# SW_Regulator.net
KiCad netlist of a schematic drawn in Altium Designer
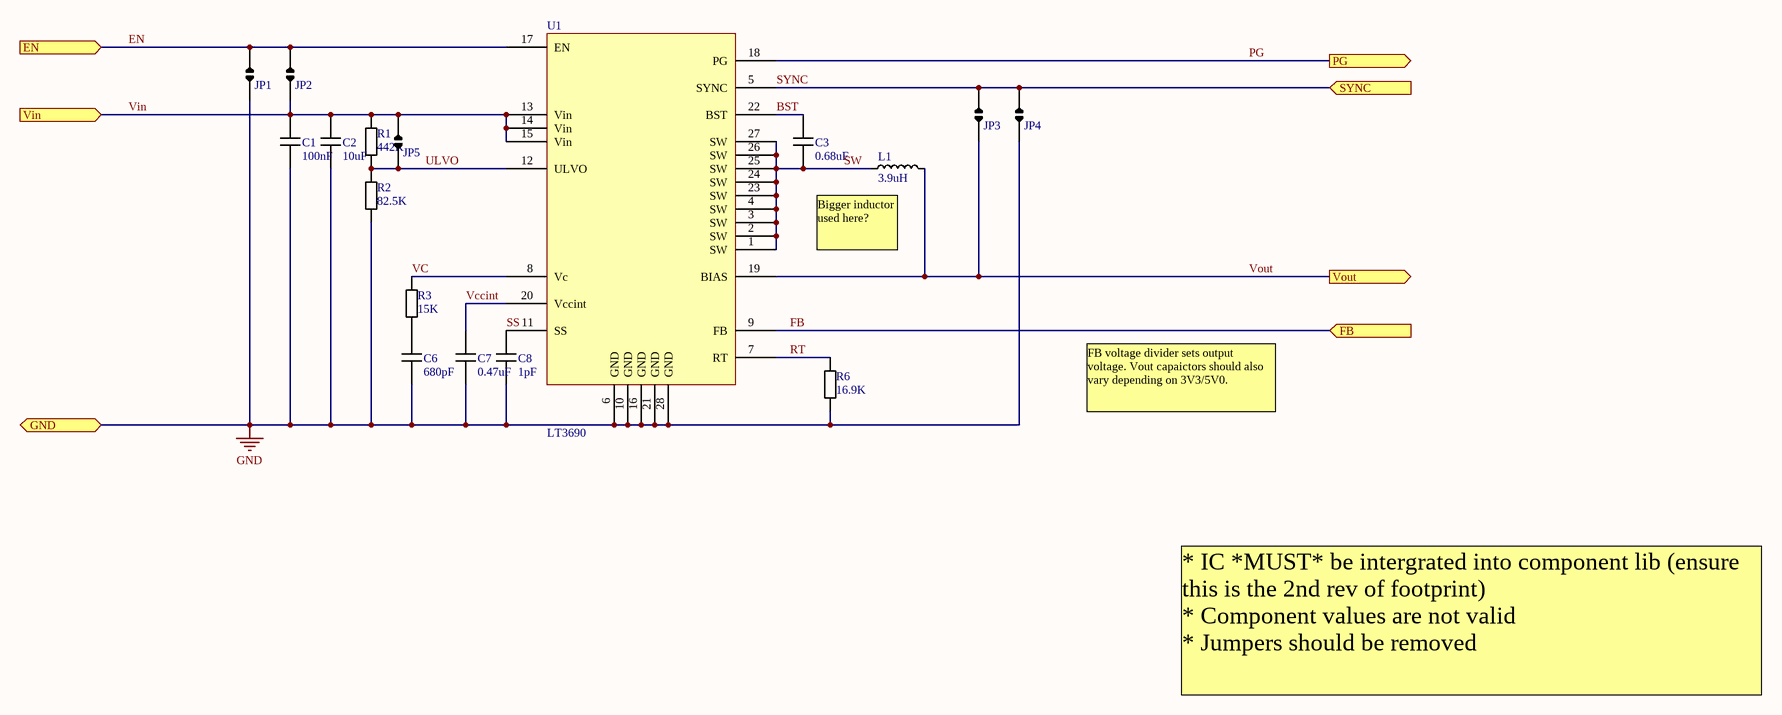
[diagram p0: SW_Regulator.SchDoc]

(export (version "E")
  (design (tool "Eeschema 10.0.6"))
  (components
    (comp (ref "C1")
      (value "100nF")
      (footprint "0805 Cap")
      (description "0805 MLCC - X7R, 10%")
      (fields (field (name "Comment") "0805 Cap"))
      (libsource (lib "Schlib1") (part "0805 MLCC - X7R, 10%"))
    )
    (comp (ref "C2")
      (value "10uF")
      (footprint "1206 Cap")
      (description "1206 MLCC - X7R, 10%")
      (fields (field (name "Comment") "1206 Cap"))
      (libsource (lib "Schlib1") (part "1206 MLCC - X7R, 10%"))
    )
    (comp (ref "C3")
      (value "0.68uF")
      (footprint "0805 Cap")
      (description "0805 MLCC - X7R, 10%")
      (fields (field (name "Comment") "0805 Cap"))
      (libsource (lib "Schlib1") (part "0805 MLCC - X7R, 10%"))
    )
    (comp (ref "C6")
      (value "680pF")
      (footprint "0805 Cap")
      (description "0805 MLCC - NP0, 5%")
      (fields (field (name "Comment") "0805 Cap"))
      (libsource (lib "Schlib1") (part "0805 MLCC - NP0, 5%"))
    )
    (comp (ref "C7")
      (value "0.47uF")
      (footprint "0805 Cap")
      (description "0805 MLCC - X7R, 10%")
      (fields (field (name "Comment") "0805 Cap"))
      (libsource (lib "Schlib1") (part "0805 MLCC - X7R, 10%"))
    )
    (comp (ref "C8")
      (value "1pF")
      (footprint "0805 Cap")
      (description "0805 MLCC - NP0, 5%")
      (fields (field (name "Comment") "0805 Cap"))
      (libsource (lib "Schlib1") (part "0805 MLCC - NP0, 5%"))
    )
    (comp (ref "JP1")
      (value "Jumper")
      (footprint "Solder Jumper C")
      (description "Solder Bridge")
      (libsource (lib "Schlib1") (part "Solder Bridge"))
    )
    (comp (ref "JP2")
      (value "Jumper")
      (footprint "Solder Jumper C")
      (description "Solder Bridge")
      (libsource (lib "Schlib1") (part "Solder Bridge"))
    )
    (comp (ref "JP3")
      (value "Jumper")
      (footprint "Solder Jumper C")
      (description "Solder Bridge")
      (libsource (lib "Schlib1") (part "Solder Bridge"))
    )
    (comp (ref "JP4")
      (value "Jumper")
      (footprint "Solder Jumper C")
      (description "Solder Bridge")
      (libsource (lib "Schlib1") (part "Solder Bridge"))
    )
    (comp (ref "JP5")
      (value "Jumper")
      (footprint "Solder Jumper C")
      (description "Solder Bridge")
      (libsource (lib "Schlib1") (part "Solder Bridge"))
    )
    (comp (ref "L1")
      (value "3.9uH")
      (footprint "INDP4037X16N")
      (description "Inductor 4x4mm 2.2uH")
      (fields (field (name "Comment") "LQH44PN2R2MP0"))
      (libsource (lib "Schlib1") (part "LQH44PN2R2MP0"))
    )
    (comp (ref "R1")
      (value "442K")
      (footprint "0805 Resistor")
      (description "0805 Thick Film Resistor 1%")
      (fields (field (name "Comment") "0805 Resistor"))
      (libsource (lib "Schlib1") (part "0805 Thick Film Resistor 1%"))
    )
    (comp (ref "R2")
      (value "82.5K")
      (footprint "0805 Resistor")
      (description "0805 Thick Film Resistor 1%")
      (fields (field (name "Comment") "0805 Resistor"))
      (libsource (lib "Schlib1") (part "0805 Thick Film Resistor 1%"))
    )
    (comp (ref "R3")
      (value "15K")
      (footprint "0805 Resistor")
      (description "0805 Thick Film Resistor 1%")
      (fields (field (name "Comment") "0805 Resistor"))
      (libsource (lib "Schlib1") (part "0805 Thick Film Resistor 1%"))
    )
    (comp (ref "R6")
      (value "16.9K")
      (footprint "0805 Resistor")
      (description "0805 Thick Film Resistor 1%")
      (fields (field (name "Comment") "0805 Resistor"))
      (libsource (lib "Schlib1") (part "0805 Thick Film Resistor 1%"))
    )
    (comp (ref "U1") (value "LT3690") (footprint "LT3690") (libsource (lib "Schlib1") (part "LT3690")))
  )
  (nets
    (net (code "1") (name "/BST") (class "Default")
      (node (ref "C3") (pin "2") (pinfunction "2_2") (pintype "passive"))
      (node (ref "U1") (pin "22") (pinfunction "BST_22") (pintype "passive"))
    )
    (net (code "2") (name "/EN") (class "Default")
      (node (ref "JP1") (pin "1") (pinfunction "1_1") (pintype "passive"))
      (node (ref "JP2") (pin "1") (pinfunction "1_1") (pintype "passive"))
      (node (ref "U1") (pin "17") (pinfunction "EN_17") (pintype "passive"))
    )
    (net (code "3") (name "/FB") (class "Default")
      (node (ref "U1") (pin "9") (pinfunction "FB_9") (pintype "passive"))
    )
    (net (code "4") (name "/PG") (class "Default")
      (node (ref "U1") (pin "18") (pinfunction "PG_18") (pintype "passive"))
    )
    (net (code "5") (name "/RT") (class "Default")
      (node (ref "R6") (pin "2") (pinfunction "2_2") (pintype "passive"))
      (node (ref "U1") (pin "7") (pinfunction "RT_7") (pintype "passive"))
    )
    (net (code "6") (name "/SS") (class "Default")
      (node (ref "C8") (pin "2") (pinfunction "2_2") (pintype "passive"))
      (node (ref "U1") (pin "11") (pinfunction "SS_11") (pintype "passive"))
    )
    (net (code "7") (name "/SW") (class "Default")
      (node (ref "C3") (pin "1") (pinfunction "1_1") (pintype "passive"))
      (node (ref "L1") (pin "1") (pinfunction "1_1") (pintype "passive"))
      (node (ref "U1") (pin "1") (pinfunction "SW_1") (pintype "passive"))
      (node (ref "U1") (pin "2") (pinfunction "SW_2") (pintype "passive"))
      (node (ref "U1") (pin "23") (pinfunction "SW_23") (pintype "passive"))
      (node (ref "U1") (pin "24") (pinfunction "SW_24") (pintype "passive"))
      (node (ref "U1") (pin "25") (pinfunction "SW_25") (pintype "passive"))
      (node (ref "U1") (pin "26") (pinfunction "SW_26") (pintype "passive"))
      (node (ref "U1") (pin "27") (pinfunction "SW_27") (pintype "passive"))
      (node (ref "U1") (pin "3") (pinfunction "SW_3") (pintype "passive"))
      (node (ref "U1") (pin "4") (pinfunction "SW_4") (pintype "passive"))
    )
    (net (code "8") (name "/SYNC") (class "Default")
      (node (ref "JP3") (pin "1") (pinfunction "1_1") (pintype "passive"))
      (node (ref "JP4") (pin "1") (pinfunction "1_1") (pintype "passive"))
      (node (ref "U1") (pin "5") (pinfunction "SYNC_5") (pintype "passive"))
    )
    (net (code "9") (name "/ULVO") (class "Default")
      (node (ref "JP5") (pin "2") (pinfunction "2_2") (pintype "passive"))
      (node (ref "R1") (pin "1") (pinfunction "1_1") (pintype "passive"))
      (node (ref "R2") (pin "2") (pinfunction "2_2") (pintype "passive"))
      (node (ref "U1") (pin "12") (pinfunction "ULVO_12") (pintype "passive"))
    )
    (net (code "10") (name "/VC") (class "Default")
      (node (ref "R3") (pin "2") (pinfunction "2_2") (pintype "passive"))
      (node (ref "U1") (pin "8") (pinfunction "Vc_8") (pintype "passive"))
    )
    (net (code "11") (name "/Vccint") (class "Default")
      (node (ref "C7") (pin "2") (pinfunction "2_2") (pintype "passive"))
      (node (ref "U1") (pin "20") (pinfunction "Vccint_20") (pintype "passive"))
    )
    (net (code "12") (name "/Vin") (class "Default")
      (node (ref "C1") (pin "2") (pinfunction "2_2") (pintype "passive"))
      (node (ref "C2") (pin "2") (pinfunction "2_2") (pintype "passive"))
      (node (ref "JP2") (pin "2") (pinfunction "2_2") (pintype "passive"))
      (node (ref "JP5") (pin "1") (pinfunction "1_1") (pintype "passive"))
      (node (ref "R1") (pin "2") (pinfunction "2_2") (pintype "passive"))
      (node (ref "U1") (pin "13") (pinfunction "Vin_13") (pintype "passive"))
      (node (ref "U1") (pin "14") (pinfunction "Vin_14") (pintype "passive"))
      (node (ref "U1") (pin "15") (pinfunction "Vin_15") (pintype "passive"))
    )
    (net (code "13") (name "/Vout") (class "Default")
      (node (ref "JP3") (pin "2") (pinfunction "2_2") (pintype "passive"))
      (node (ref "L1") (pin "2") (pinfunction "2_2") (pintype "passive"))
      (node (ref "U1") (pin "19") (pinfunction "BIAS_19") (pintype "passive"))
    )
    (net (code "14") (name "GND") (class "Default")
      (node (ref "C1") (pin "1") (pinfunction "1_1") (pintype "passive"))
      (node (ref "C2") (pin "1") (pinfunction "1_1") (pintype "passive"))
      (node (ref "C6") (pin "1") (pinfunction "1_1") (pintype "passive"))
      (node (ref "C7") (pin "1") (pinfunction "1_1") (pintype "passive"))
      (node (ref "C8") (pin "1") (pinfunction "1_1") (pintype "passive"))
      (node (ref "JP1") (pin "2") (pinfunction "2_2") (pintype "passive"))
      (node (ref "JP4") (pin "2") (pinfunction "2_2") (pintype "passive"))
      (node (ref "R2") (pin "1") (pinfunction "1_1") (pintype "passive"))
      (node (ref "R6") (pin "1") (pinfunction "1_1") (pintype "passive"))
      (node (ref "U1") (pin "10") (pinfunction "GND_10") (pintype "passive"))
      (node (ref "U1") (pin "16") (pinfunction "GND_16") (pintype "passive"))
      (node (ref "U1") (pin "21") (pinfunction "GND_21") (pintype "passive"))
      (node (ref "U1") (pin "28") (pinfunction "GND_28") (pintype "passive"))
      (node (ref "U1") (pin "6") (pinfunction "GND_6") (pintype "passive"))
    )
    (net (code "15") (name "Net-(C6-Pad2)") (class "Default")
      (node (ref "C6") (pin "2") (pinfunction "2_2") (pintype "passive"))
      (node (ref "R3") (pin "1") (pinfunction "1_1") (pintype "passive"))
    )
  )
)
